# Anemoia-ESP32-SMD.net
KiCad netlist of a schematic drawn in Altium Designer
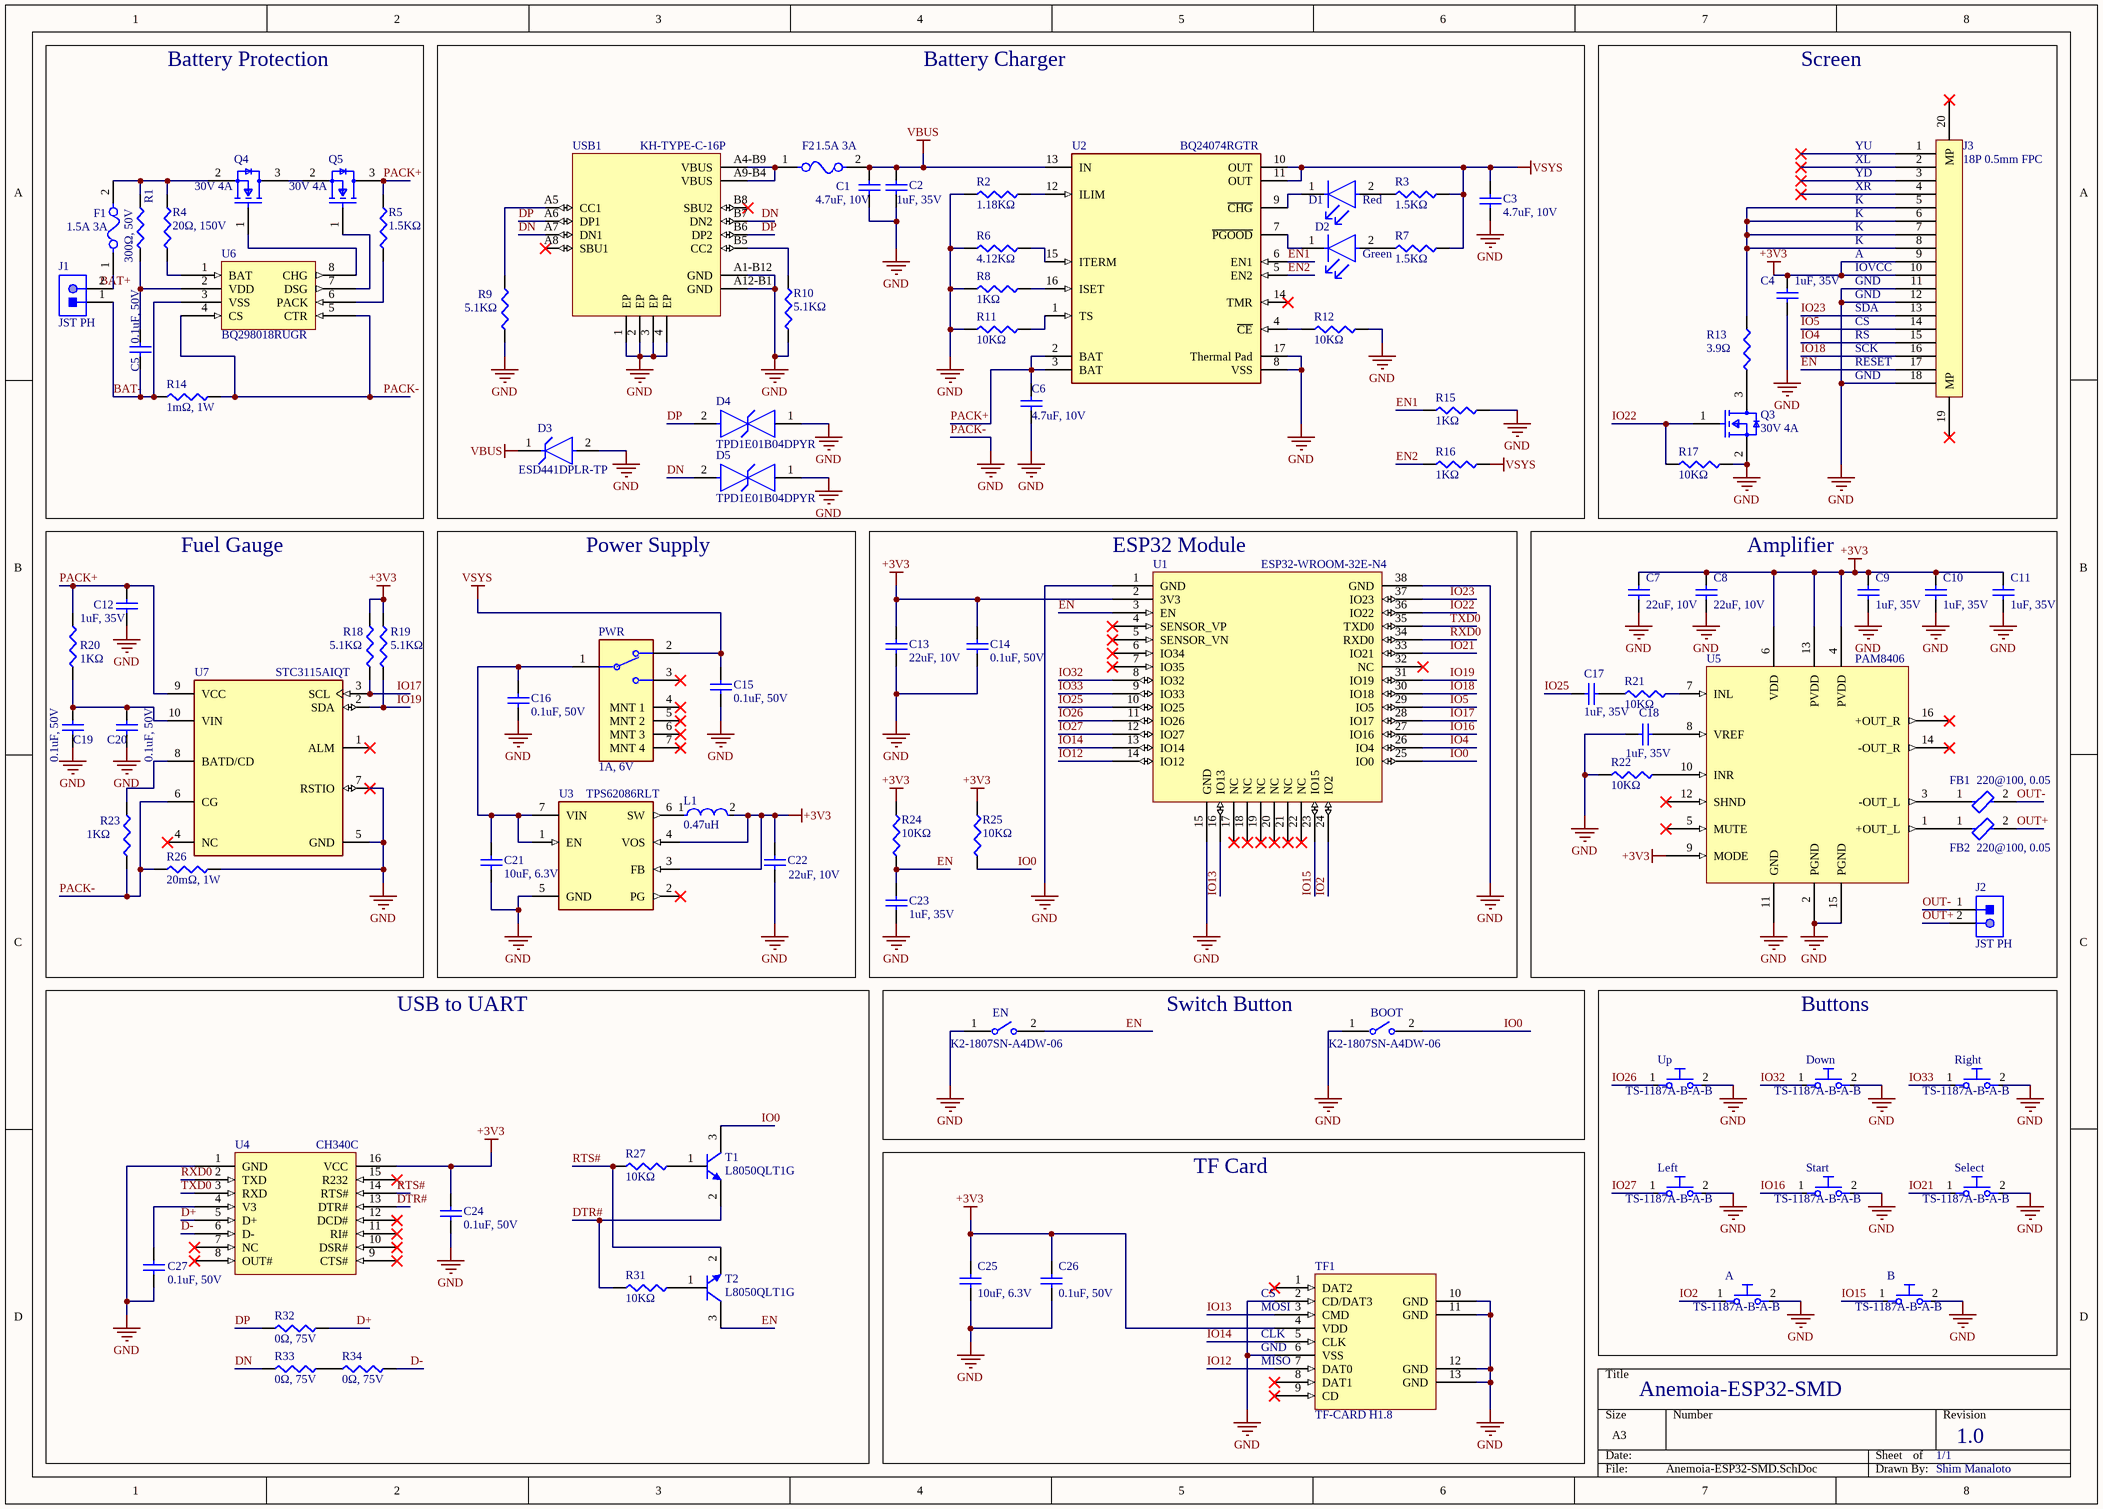
[diagram p0: Anemoia-ESP32-SMD.SchDoc]

(export (version "E")
  (design (tool "Eeschema 10.0.6"))
  (components
    (comp (ref "A")
      (value "TS-1187A-B-A-B")
      (footprint "SWITCH TACTILE SMD-4P,5.1x5.1mm")
      (description "Without Bracket 5.1mm 12V 5.1mm Round Button No SPST 50mA SMD-4P,5.1x5.1mm Tactile Switches RoHS")
      (libsource (lib "Anemoia-ESP32") (part "TS-1187A-B-A-B"))
    )
    (comp (ref "B")
      (value "TS-1187A-B-A-B")
      (footprint "SWITCH TACTILE SMD-4P,5.1x5.1mm")
      (description "Without Bracket 5.1mm 12V 5.1mm Round Button No SPST 50mA SMD-4P,5.1x5.1mm Tactile Switches RoHS")
      (libsource (lib "Anemoia-ESP32") (part "TS-1187A-B-A-B"))
    )
    (comp (ref "BOOT")
      (value "K2-1807SN-A4DW-06")
      (footprint "SWITCH TACTILE MD,4x2.9mm")
      (description "12V 2.9mm 4mm 50mA SMD,4x2.9mm Tactile Switches RoHS")
      (libsource (lib "Anemoia-ESP32") (part "K2-1807SN-A4DW-06"))
    )
    (comp (ref "C1")
      (value "4.7uF, 10V")
      (footprint "CAP CER 0603")
      (description "CAP CER 4.7uF 10V ±10% X5R 0603")
      (fields
        (field (name "MANUFACTURER") "Samsung Electro-Mechanics")
        (field (name "MANUFACTURER PART NUMBER") "CL10A475KP8NNNC")
      )
      (libsource (lib "Anemoia-ESP32") (part "CL10A475KP8NNNC"))
    )
    (comp (ref "C2")
      (value "1uF, 35V")
      (footprint "CAP CER SAMSUNG 0402")
      (description "CAP CER 1uF 35V ±10% X5R 0402")
      (fields
        (field (name "MANUFACTURER") "Samsung Electro-Mechanics")
        (field (name "MANUFACTURER PART NUMBER") "CL05A105KP5NNNC")
      )
      (libsource (lib "Anemoia-ESP32") (part "CL05A105KL5NRNC"))
    )
    (comp (ref "C3")
      (value "4.7uF, 10V")
      (footprint "CAP CER 0603")
      (description "CAP CER 4.7uF 10V ±10% X5R 0603")
      (fields
        (field (name "MANUFACTURER") "Samsung Electro-Mechanics")
        (field (name "MANUFACTURER PART NUMBER") "CL10A475KP8NNNC")
      )
      (libsource (lib "Anemoia-ESP32") (part "CL10A475KP8NNNC"))
    )
    (comp (ref "C4")
      (value "1uF, 35V")
      (footprint "CAP CER SAMSUNG 0402")
      (description "CAP CER 1uF 35V ±10% X5R 0402")
      (fields
        (field (name "MANUFACTURER") "Samsung Electro-Mechanics")
        (field (name "MANUFACTURER PART NUMBER") "CL05A105KP5NNNC")
      )
      (libsource (lib "Anemoia-ESP32") (part "CL05A105KL5NRNC"))
    )
    (comp (ref "C5")
      (value "0.1uF, 50V")
      (footprint "CAP CER 0603")
      (description "CAP CER 0.1UF 50V X7R 0603")
      (fields
        (field (name "MANUFACTURER") "Yageo Group")
        (field (name "MANUFACTURER PART NUMBER") "CC0603KRX7R9BB104")
      )
      (libsource (lib "Anemoia-ESP32") (part "CC0603KRX7R9BB104"))
    )
    (comp (ref "C6")
      (value "4.7uF, 10V")
      (footprint "CAP CER 0603")
      (description "CAP CER 4.7uF 10V ±10% X5R 0603")
      (fields
        (field (name "MANUFACTURER") "Samsung Electro-Mechanics")
        (field (name "MANUFACTURER PART NUMBER") "CL10A475KP8NNNC")
      )
      (libsource (lib "Anemoia-ESP32") (part "CL10A475KP8NNNC"))
    )
    (comp (ref "C7")
      (value "22uF, 10V")
      (footprint "CAP CER 0603")
      (description "CAP CER 22UF 10V X5R 0603")
      (fields
        (field (name "MANUFACTURER") "Murata")
        (field (name "MANUFACTURER PART NUMBER") "GRM188R61A226ME15D")
      )
      (libsource (lib "Anemoia-ESP32") (part "GRM188R61A226ME15D"))
    )
    (comp (ref "C8")
      (value "22uF, 10V")
      (footprint "CAP CER 0603")
      (description "CAP CER 22UF 10V X5R 0603")
      (fields
        (field (name "MANUFACTURER") "Murata")
        (field (name "MANUFACTURER PART NUMBER") "GRM188R61A226ME15D")
      )
      (libsource (lib "Anemoia-ESP32") (part "GRM188R61A226ME15D"))
    )
    (comp (ref "C9")
      (value "1uF, 35V")
      (footprint "CAP CER SAMSUNG 0402")
      (description "CAP CER 1uF 35V ±10% X5R 0402")
      (fields
        (field (name "MANUFACTURER") "Samsung Electro-Mechanics")
        (field (name "MANUFACTURER PART NUMBER") "CL05A105KP5NNNC")
      )
      (libsource (lib "Anemoia-ESP32") (part "CL05A105KL5NRNC"))
    )
    (comp (ref "C10")
      (value "1uF, 35V")
      (footprint "CAP CER SAMSUNG 0402")
      (description "CAP CER 1uF 35V ±10% X5R 0402")
      (fields
        (field (name "MANUFACTURER") "Samsung Electro-Mechanics")
        (field (name "MANUFACTURER PART NUMBER") "CL05A105KP5NNNC")
      )
      (libsource (lib "Anemoia-ESP32") (part "CL05A105KL5NRNC"))
    )
    (comp (ref "C11")
      (value "1uF, 35V")
      (footprint "CAP CER SAMSUNG 0402")
      (description "CAP CER 1uF 35V ±10% X5R 0402")
      (fields
        (field (name "MANUFACTURER") "Samsung Electro-Mechanics")
        (field (name "MANUFACTURER PART NUMBER") "CL05A105KP5NNNC")
      )
      (libsource (lib "Anemoia-ESP32") (part "CL05A105KL5NRNC"))
    )
    (comp (ref "C12")
      (value "1uF, 35V")
      (footprint "CAP CER SAMSUNG 0402")
      (description "CAP CER 1uF 35V ±10% X5R 0402")
      (fields
        (field (name "MANUFACTURER") "Samsung Electro-Mechanics")
        (field (name "MANUFACTURER PART NUMBER") "CL05A105KP5NNNC")
      )
      (libsource (lib "Anemoia-ESP32") (part "CL05A105KL5NRNC"))
    )
    (comp (ref "C13")
      (value "22uF, 10V")
      (footprint "CAP CER 0603")
      (description "CAP CER 22UF 10V X5R 0603")
      (fields
        (field (name "MANUFACTURER") "Murata")
        (field (name "MANUFACTURER PART NUMBER") "GRM188R61A226ME15D")
      )
      (libsource (lib "Anemoia-ESP32") (part "GRM188R61A226ME15D"))
    )
    (comp (ref "C14")
      (value "0.1uF, 50V")
      (footprint "CAP CER 0603")
      (description "CAP CER 0.1UF 50V X7R 0603")
      (fields
        (field (name "MANUFACTURER") "Yageo Group")
        (field (name "MANUFACTURER PART NUMBER") "CC0603KRX7R9BB104")
      )
      (libsource (lib "Anemoia-ESP32") (part "CC0603KRX7R9BB104"))
    )
    (comp (ref "C15")
      (value "0.1uF, 50V")
      (footprint "CAP CER 0603")
      (description "CAP CER 0.1UF 50V X7R 0603")
      (fields
        (field (name "MANUFACTURER") "Yageo Group")
        (field (name "MANUFACTURER PART NUMBER") "CC0603KRX7R9BB104")
      )
      (libsource (lib "Anemoia-ESP32") (part "CC0603KRX7R9BB104"))
    )
    (comp (ref "C16")
      (value "0.1uF, 50V")
      (footprint "CAP CER 0603")
      (description "CAP CER 0.1UF 50V X7R 0603")
      (fields
        (field (name "MANUFACTURER") "Yageo Group")
        (field (name "MANUFACTURER PART NUMBER") "CC0603KRX7R9BB104")
      )
      (libsource (lib "Anemoia-ESP32") (part "CC0603KRX7R9BB104"))
    )
    (comp (ref "C17")
      (value "1uF, 35V")
      (footprint "CAP CER SAMSUNG 0402")
      (description "CAP CER 1uF 35V ±10% X5R 0402")
      (fields
        (field (name "MANUFACTURER") "Samsung Electro-Mechanics")
        (field (name "MANUFACTURER PART NUMBER") "CL05A105KP5NNNC")
      )
      (libsource (lib "Anemoia-ESP32") (part "CL05A105KL5NRNC"))
    )
    (comp (ref "C18")
      (value "1uF, 35V")
      (footprint "CAP CER SAMSUNG 0402")
      (description "CAP CER 1uF 35V ±10% X5R 0402")
      (fields
        (field (name "MANUFACTURER") "Samsung Electro-Mechanics")
        (field (name "MANUFACTURER PART NUMBER") "CL05A105KP5NNNC")
      )
      (libsource (lib "Anemoia-ESP32") (part "CL05A105KL5NRNC"))
    )
    (comp (ref "C19")
      (value "0.1uF, 50V")
      (footprint "CAP CER 0603")
      (description "CAP CER 0.1UF 50V X7R 0603")
      (fields
        (field (name "MANUFACTURER") "Yageo Group")
        (field (name "MANUFACTURER PART NUMBER") "CC0603KRX7R9BB104")
      )
      (libsource (lib "Anemoia-ESP32") (part "CC0603KRX7R9BB104"))
    )
    (comp (ref "C20")
      (value "0.1uF, 50V")
      (footprint "CAP CER 0603")
      (description "CAP CER 0.1UF 50V X7R 0603")
      (fields
        (field (name "MANUFACTURER") "Yageo Group")
        (field (name "MANUFACTURER PART NUMBER") "CC0603KRX7R9BB104")
      )
      (libsource (lib "Anemoia-ESP32") (part "CC0603KRX7R9BB104"))
    )
    (comp (ref "C21")
      (value "10uF, 6.3V")
      (footprint "CAP CER SAMSUNG 0402")
      (description "6.3V 10uF X5R ±20% 0402 Ceramic Capacitors RoHS")
      (fields
        (field (name "MANUFACTURER") "Samsung Electro-Mechanics")
        (field (name "MANUFACTURER PART NUMBER") "CL05A106MQ5NUNC")
      )
      (libsource (lib "Anemoia-ESP32") (part "CL05A106MQ5NUNC"))
    )
    (comp (ref "C22")
      (value "22uF, 10V")
      (footprint "CAP CER 0603")
      (description "CAP CER 22UF 10V X5R 0603")
      (fields
        (field (name "MANUFACTURER") "Murata")
        (field (name "MANUFACTURER PART NUMBER") "GRM188R61A226ME15D")
      )
      (libsource (lib "Anemoia-ESP32") (part "GRM188R61A226ME15D"))
    )
    (comp (ref "C23")
      (value "1uF, 35V")
      (footprint "CAP CER SAMSUNG 0402")
      (description "CAP CER 1uF 35V ±10% X5R 0402")
      (fields
        (field (name "MANUFACTURER") "Samsung Electro-Mechanics")
        (field (name "MANUFACTURER PART NUMBER") "CL05A105KP5NNNC")
      )
      (libsource (lib "Anemoia-ESP32") (part "CL05A105KL5NRNC"))
    )
    (comp (ref "C24")
      (value "0.1uF, 50V")
      (footprint "CAP CER 0603")
      (description "CAP CER 0.1UF 50V X7R 0603")
      (fields
        (field (name "MANUFACTURER") "Yageo Group")
        (field (name "MANUFACTURER PART NUMBER") "CC0603KRX7R9BB104")
      )
      (libsource (lib "Anemoia-ESP32") (part "CC0603KRX7R9BB104"))
    )
    (comp (ref "C25")
      (value "10uF, 6.3V")
      (footprint "CAP CER SAMSUNG 0402")
      (description "6.3V 10uF X5R ±20% 0402 Ceramic Capacitors RoHS")
      (fields
        (field (name "MANUFACTURER") "Samsung Electro-Mechanics")
        (field (name "MANUFACTURER PART NUMBER") "CL05A106MQ5NUNC")
      )
      (libsource (lib "Anemoia-ESP32") (part "CL05A106MQ5NUNC"))
    )
    (comp (ref "C26")
      (value "0.1uF, 50V")
      (footprint "CAP CER 0603")
      (description "CAP CER 0.1UF 50V X7R 0603")
      (fields
        (field (name "MANUFACTURER") "Yageo Group")
        (field (name "MANUFACTURER PART NUMBER") "CC0603KRX7R9BB104")
      )
      (libsource (lib "Anemoia-ESP32") (part "CC0603KRX7R9BB104"))
    )
    (comp (ref "C27")
      (value "0.1uF, 50V")
      (footprint "CAP CER 0603")
      (description "CAP CER 0.1UF 50V X7R 0603")
      (fields
        (field (name "MANUFACTURER") "Yageo Group")
        (field (name "MANUFACTURER PART NUMBER") "CC0603KRX7R9BB104")
      )
      (libsource (lib "Anemoia-ESP32") (part "CC0603KRX7R9BB104"))
    )
    (comp (ref "D1")
      (value "Red")
      (footprint "Red LED 0603")
      (description "LED RED WATER CLEAR 0603 SMD")
      (libsource (lib "Anemoia-ESP32") (part "XL-1608SURC-06"))
    )
    (comp (ref "D2")
      (value "Green")
      (footprint "Green LED 0603")
      (description "LED GREEN WATER CLEAR 0603 SMD")
      (libsource (lib "Anemoia-ESP32") (part "PSC-1608U52GC-G4"))
    )
    (comp (ref "D3")
      (value "ESD441DPLR-TP")
      (footprint "DFN0603-2")
      (description "ESD DIODE 5.5VWM 20VC DFN0603-2")
      (libsource (lib "Anemoia-ESP32") (part "ESD441DPLR-TP"))
    )
    (comp (ref "D4")
      (value "TPD1E01B04DPYR")
      (footprint "X1-SON-2")
      (description "3.6VWM 9VC X1SON-2(0.6x1)")
      (libsource (lib "Anemoia-ESP32") (part "TPD1E01B04DPYR"))
    )
    (comp (ref "D5")
      (value "TPD1E01B04DPYR")
      (footprint "X1-SON-2")
      (description "3.6VWM 9VC X1SON-2(0.6x1)")
      (libsource (lib "Anemoia-ESP32") (part "TPD1E01B04DPYR"))
    )
    (comp (ref "Down")
      (value "TS-1187A-B-A-B")
      (footprint "SWITCH TACTILE SMD-4P,5.1x5.1mm")
      (description "Without Bracket 5.1mm 12V 5.1mm Round Button No SPST 50mA SMD-4P,5.1x5.1mm Tactile Switches RoHS")
      (libsource (lib "Anemoia-ESP32") (part "TS-1187A-B-A-B"))
    )
    (comp (ref "EN")
      (value "K2-1807SN-A4DW-06")
      (footprint "SWITCH TACTILE MD,4x2.9mm")
      (description "12V 2.9mm 4mm 50mA SMD,4x2.9mm Tactile Switches RoHS")
      (libsource (lib "Anemoia-ESP32") (part "K2-1807SN-A4DW-06"))
    )
    (comp (ref "F1")
      (value "1.5A 3A")
      (footprint "PTC 1812")
      (description "24V 1.5A 20A 3A 40mΩ 1812 PTC Resettable Fuses RoHS")
      (fields
        (field (name "MANUFACTURER") "Littelfuse")
        (field (name "MANUFACTURER PART NUMBER") "1812L150/24MR")
      )
      (libsource (lib "Anemoia-ESP32") (part "1812L150/24MR"))
    )
    (comp (ref "F2")
      (value "1.5A 3A")
      (footprint "PTC 1812")
      (description "24V 1.5A 20A 3A 40mΩ 1812 PTC Resettable Fuses RoHS")
      (fields
        (field (name "MANUFACTURER") "Littelfuse")
        (field (name "MANUFACTURER PART NUMBER") "1812L150/24MR")
      )
      (libsource (lib "Anemoia-ESP32") (part "1812L150/24MR"))
    )
    (comp (ref "FB1")
      (value "220@100, 0.05")
      (footprint "0603 FB")
      (description "Chip Ferrite Bead, 0603, 220Ω @ 100MHz, 0.05Ω, 25%, 2A")
      (fields
        (field (name "MANUFACTURER") "Murata")
        (field (name "MANUFACTURER PART NUMBER") "BLM18EG221SN1D")
      )
      (libsource (lib "Anemoia-ESP32") (part "BLM18EG221SN1D"))
    )
    (comp (ref "FB2")
      (value "220@100, 0.05")
      (footprint "0603 FB")
      (description "Chip Ferrite Bead, 0603, 220Ω @ 100MHz, 0.05Ω, 25%, 2A")
      (fields
        (field (name "MANUFACTURER") "Murata")
        (field (name "MANUFACTURER PART NUMBER") "BLM18EG221SN1D")
      )
      (libsource (lib "Anemoia-ESP32") (part "BLM18EG221SN1D"))
    )
    (comp (ref "J1")
      (value "JST PH")
      (footprint "JST_S2B-PH-SM4-TB(LF)(SN)")
      (fields
        (field (name "MANUFACTURER") "JST")
        (field (name "MANUFACTURER PART NUMBER") "S2B-PH-SM4-TB(LF)(SN)")
      )
      (libsource (lib "") (part "S2B-PH-SM4-TB(LF)(SN)_1"))
    )
    (comp (ref "J2")
      (value "JST PH")
      (footprint "JST_S2B-PH-SM4-TB(LF)(SN)")
      (fields
        (field (name "MANUFACTURER") "JST")
        (field (name "MANUFACTURER PART NUMBER") "S2B-PH-SM4-TB(LF)(SN)")
      )
      (libsource (lib "Anemoia-ESP32") (part "S2B-PH-SM4-TB(LF)(SN)"))
    )
    (comp (ref "J3")
      (value "18P 0.5mm FPC")
      (footprint "FPC CN 18P 0.5mm")
      (description "CONN FFC FPC 18POS 0.5mm BOTTOM CNT SMD R/A")
      (libsource (lib "Anemoia-ESP32") (part "HC-FPC-0.5-18P-CXH20"))
    )
    (comp (ref "L1")
      (value "0.47uH")
      (footprint "SMD,4x4mm")
      (description "FIXED IND 470nH SMD,4x4mm")
      (libsource (lib "Anemoia-ESP32") (part "XFL4015-471MEC"))
    )
    (comp (ref "Left")
      (value "TS-1187A-B-A-B")
      (footprint "SWITCH TACTILE SMD-4P,5.1x5.1mm")
      (description "Without Bracket 5.1mm 12V 5.1mm Round Button No SPST 50mA SMD-4P,5.1x5.1mm Tactile Switches RoHS")
      (libsource (lib "Anemoia-ESP32") (part "TS-1187A-B-A-B"))
    )
    (comp (ref "PWR")
      (value "1A, 6V")
      (footprint "MK-12C02-G020")
      (description "Surface Mount, Right Angle 1A SPDT 6V Black 10,000 Cycles SMD,6.6x1.4mm Slide Switches RoHS")
      (libsource (lib "Anemoia-ESP32") (part "MK-12C02-G020"))
    )
    (comp (ref "Q3")
      (value "30V 4A")
      (footprint "SOT-23")
      (description "MOSFET N-CH 30V SOT-23")
      (libsource (lib "Anemoia-ESP32") (part "AO3402"))
    )
    (comp (ref "Q4")
      (value "30V 4A")
      (footprint "SOT-23")
      (description "MOSFET N-CH 30V SOT-23")
      (libsource (lib "Anemoia-ESP32") (part "AO3402"))
    )
    (comp (ref "Q5")
      (value "30V 4A")
      (footprint "SOT-23")
      (description "MOSFET N-CH 30V SOT-23")
      (libsource (lib "Anemoia-ESP32") (part "AO3402"))
    )
    (comp (ref "R1")
      (value "300Ω, 50V")
      (footprint "RES 0402")
      (description "RES 300Ω ±1% 62.5mW 0402")
      (libsource (lib "Anemoia-ESP32") (part "RC0402FR-07300RL"))
    )
    (comp (ref "R2")
      (value "1.18KΩ")
      (footprint "RES 0402")
      (description "RES 1.18kΩ ±1% 62.5mW 0402")
      (libsource (lib "Anemoia-ESP32") (part "RC0402FR-071K18L"))
    )
    (comp (ref "R3")
      (value "1.5KΩ")
      (footprint "RES 0603")
      (description "RES 1.5kΩ ±1% 100mW 0603")
      (libsource (lib "Anemoia-ESP32") (part "RC0603FR-071K5L"))
    )
    (comp (ref "R4")
      (value "20Ω, 150V")
      (footprint "RES 0805")
      (description "RES 20Ω ±1% 125mW 0805")
      (libsource (lib "Anemoia-ESP32") (part "RC0805FR-0720RL"))
    )
    (comp (ref "R5")
      (value "1.5KΩ")
      (footprint "RES 0603")
      (description "RES 1.5kΩ ±1% 100mW 0603")
      (libsource (lib "Anemoia-ESP32") (part "RC0603FR-071K5L"))
    )
    (comp (ref "R6")
      (value "4.12KΩ")
      (footprint "RES 0402")
      (description "RES 4.12kΩ ±1% 62.5mW 0402")
      (libsource (lib "Anemoia-ESP32") (part "RC0402FR-074K12L"))
    )
    (comp (ref "R7")
      (value "1.5KΩ")
      (footprint "RES 0603")
      (description "RES 1.5kΩ ±1% 100mW 0603")
      (libsource (lib "Anemoia-ESP32") (part "RC0603FR-071K5L"))
    )
    (comp (ref "R8")
      (value "1KΩ")
      (footprint "RES 0402")
      (description "RES 1kΩ ±1% 62.5mW 0402")
      (fields
        (field (name "MANUFACTURER") "Yageo Group")
        (field (name "MANUFACTURER PART NUMBER") "RC0402FR-071KL")
      )
      (libsource (lib "Anemoia-ESP32") (part "RC0402FR-071KL"))
    )
    (comp (ref "R9")
      (value "5.1KΩ")
      (footprint "RES 0402")
      (description "RES 5.1kΩ ±1% 62.5mW 0402")
      (libsource (lib "Anemoia-ESP32") (part "RC0402FR-075K1L"))
    )
    (comp (ref "R10")
      (value "5.1KΩ")
      (footprint "RES 0402")
      (description "RES 5.1kΩ ±1% 62.5mW 0402")
      (libsource (lib "Anemoia-ESP32") (part "RC0402FR-075K1L"))
    )
    (comp (ref "R11")
      (value "10KΩ")
      (footprint "RES 0402")
      (description "RES 10K OHM 1% 1/16W 0402")
      (fields
        (field (name "MANUFACTURER") "Yageo Group")
        (field (name "MANUFACTURER PART NUMBER") "RC0402FR-0710KL")
      )
      (libsource (lib "Anemoia-ESP32") (part "RC0402FR-0710KL"))
    )
    (comp (ref "R12")
      (value "10KΩ")
      (footprint "RES 0402")
      (description "RES 10K OHM 1% 1/16W 0402")
      (fields
        (field (name "MANUFACTURER") "Yageo Group")
        (field (name "MANUFACTURER PART NUMBER") "RC0402FR-0710KL")
      )
      (libsource (lib "Anemoia-ESP32") (part "RC0402FR-0710KL"))
    )
    (comp (ref "R13")
      (value "3.9Ω")
      (footprint "RES 0612")
      (description "RES 3.9Ω ±5% 750mW 0612")
      (fields (field (name "MANUFACTURER") "ROHM") (field (name "MANUFACTURER PART NUMBER") "LTR18EZPJ3R9"))
      (libsource (lib "Anemoia-ESP32") (part "LTR18EZPJ3R9"))
    )
    (comp (ref "R14")
      (value "1mΩ, 1W")
      (footprint "RES 1206")
      (description "RES 1mΩ ±1% 1W 1206")
      (libsource (lib "Anemoia-ESP32") (part "FRM121WFR001TM"))
    )
    (comp (ref "R15")
      (value "1KΩ")
      (footprint "RES 0402")
      (description "RES 1kΩ ±1% 62.5mW 0402")
      (fields
        (field (name "MANUFACTURER") "Yageo Group")
        (field (name "MANUFACTURER PART NUMBER") "RC0402FR-071KL")
      )
      (libsource (lib "Anemoia-ESP32") (part "RC0402FR-071KL"))
    )
    (comp (ref "R16")
      (value "1KΩ")
      (footprint "RES 0402")
      (description "RES 1kΩ ±1% 62.5mW 0402")
      (fields
        (field (name "MANUFACTURER") "Yageo Group")
        (field (name "MANUFACTURER PART NUMBER") "RC0402FR-071KL")
      )
      (libsource (lib "Anemoia-ESP32") (part "RC0402FR-071KL"))
    )
    (comp (ref "R17")
      (value "10KΩ")
      (footprint "RES 0402")
      (description "RES 10K OHM 1% 1/16W 0402")
      (fields
        (field (name "MANUFACTURER") "Yageo Group")
        (field (name "MANUFACTURER PART NUMBER") "RC0402FR-0710KL")
      )
      (libsource (lib "Anemoia-ESP32") (part "RC0402FR-0710KL"))
    )
    (comp (ref "R18")
      (value "5.1KΩ")
      (footprint "RES 0402")
      (description "RES 5.1kΩ ±1% 62.5mW 0402")
      (libsource (lib "Anemoia-ESP32") (part "RC0402FR-075K1L"))
    )
    (comp (ref "R19")
      (value "5.1KΩ")
      (footprint "RES 0402")
      (description "RES 5.1kΩ ±1% 62.5mW 0402")
      (libsource (lib "Anemoia-ESP32") (part "RC0402FR-075K1L"))
    )
    (comp (ref "R20")
      (value "1KΩ")
      (footprint "RES 0402")
      (description "RES 1kΩ ±1% 62.5mW 0402")
      (fields
        (field (name "MANUFACTURER") "Yageo Group")
        (field (name "MANUFACTURER PART NUMBER") "RC0402FR-071KL")
      )
      (libsource (lib "Anemoia-ESP32") (part "RC0402FR-071KL"))
    )
    (comp (ref "R21")
      (value "10KΩ")
      (footprint "RES 0402")
      (description "RES 10K OHM 1% 1/16W 0402")
      (fields
        (field (name "MANUFACTURER") "Yageo Group")
        (field (name "MANUFACTURER PART NUMBER") "RC0402FR-0710KL")
      )
      (libsource (lib "Anemoia-ESP32") (part "RC0402FR-0710KL"))
    )
    (comp (ref "R22")
      (value "10KΩ")
      (footprint "RES 0402")
      (description "RES 10K OHM 1% 1/16W 0402")
      (fields
        (field (name "MANUFACTURER") "Yageo Group")
        (field (name "MANUFACTURER PART NUMBER") "RC0402FR-0710KL")
      )
      (libsource (lib "Anemoia-ESP32") (part "RC0402FR-0710KL"))
    )
    (comp (ref "R23")
      (value "1KΩ")
      (footprint "RES 0402")
      (description "RES 1kΩ ±1% 62.5mW 0402")
      (fields
        (field (name "MANUFACTURER") "Yageo Group")
        (field (name "MANUFACTURER PART NUMBER") "RC0402FR-071KL")
      )
      (libsource (lib "Anemoia-ESP32") (part "RC0402FR-071KL"))
    )
    (comp (ref "R24")
      (value "10KΩ")
      (footprint "RES 0402")
      (description "RES 10K OHM 1% 1/16W 0402")
      (fields
        (field (name "MANUFACTURER") "Yageo Group")
        (field (name "MANUFACTURER PART NUMBER") "RC0402FR-0710KL")
      )
      (libsource (lib "Anemoia-ESP32") (part "RC0402FR-0710KL"))
    )
    (comp (ref "R25")
      (value "10KΩ")
      (footprint "RES 0402")
      (description "RES 10K OHM 1% 1/16W 0402")
      (fields
        (field (name "MANUFACTURER") "Yageo Group")
        (field (name "MANUFACTURER PART NUMBER") "RC0402FR-0710KL")
      )
      (libsource (lib "Anemoia-ESP32") (part "RC0402FR-0710KL"))
    )
    (comp (ref "R26")
      (value "20mΩ, 1W")
      (footprint "RES 1206")
      (description "RES 20mΩ ±1% 1W 1206")
      (libsource (lib "Anemoia-ESP32") (part "FRM121WFR020TM"))
    )
    (comp (ref "R27")
      (value "10KΩ")
      (footprint "RES 0402")
      (description "RES 10K OHM 1% 1/16W 0402")
      (fields
        (field (name "MANUFACTURER") "Yageo Group")
        (field (name "MANUFACTURER PART NUMBER") "RC0402FR-0710KL")
      )
      (libsource (lib "Anemoia-ESP32") (part "RC0402FR-0710KL"))
    )
    (comp (ref "R31")
      (value "10KΩ")
      (footprint "RES 0402")
      (description "RES 10K OHM 1% 1/16W 0402")
      (fields
        (field (name "MANUFACTURER") "Yageo Group")
        (field (name "MANUFACTURER PART NUMBER") "RC0402FR-0710KL")
      )
      (libsource (lib "Anemoia-ESP32") (part "RC0402FR-0710KL"))
    )
    (comp (ref "R32")
      (value "0Ω, 75V")
      (footprint "RES 0OHM")
      (description "RES 0Ω ±1% 100mW 0603")
      (fields
        (field (name "MANUFACTURER") "Yageo Group")
        (field (name "MANUFACTURER PART NUMBER") "RC0603FR-070RL")
      )
      (libsource (lib "Anemoia-ESP32") (part "RC0603FR-070RL"))
    )
    (comp (ref "R33")
      (value "0Ω, 75V")
      (footprint "RES 0OHM")
      (description "RES 0Ω ±1% 100mW 0603")
      (fields
        (field (name "MANUFACTURER") "Yageo Group")
        (field (name "MANUFACTURER PART NUMBER") "RC0603FR-070RL")
      )
      (libsource (lib "Anemoia-ESP32") (part "RC0603FR-070RL"))
    )
    (comp (ref "R34")
      (value "0Ω, 75V")
      (footprint "RES 0OHM")
      (description "RES 0Ω ±1% 100mW 0603")
      (fields
        (field (name "MANUFACTURER") "Yageo Group")
        (field (name "MANUFACTURER PART NUMBER") "RC0603FR-070RL")
      )
      (libsource (lib "Anemoia-ESP32") (part "RC0603FR-070RL"))
    )
    (comp (ref "Right")
      (value "TS-1187A-B-A-B")
      (footprint "SWITCH TACTILE SMD-4P,5.1x5.1mm")
      (description "Without Bracket 5.1mm 12V 5.1mm Round Button No SPST 50mA SMD-4P,5.1x5.1mm Tactile Switches RoHS")
      (libsource (lib "Anemoia-ESP32") (part "TS-1187A-B-A-B"))
    )
    (comp (ref "Select")
      (value "TS-1187A-B-A-B")
      (footprint "SWITCH TACTILE SMD-4P,5.1x5.1mm")
      (description "Without Bracket 5.1mm 12V 5.1mm Round Button No SPST 50mA SMD-4P,5.1x5.1mm Tactile Switches RoHS")
      (libsource (lib "Anemoia-ESP32") (part "TS-1187A-B-A-B"))
    )
    (comp (ref "Start")
      (value "TS-1187A-B-A-B")
      (footprint "SWITCH TACTILE SMD-4P,5.1x5.1mm")
      (description "Without Bracket 5.1mm 12V 5.1mm Round Button No SPST 50mA SMD-4P,5.1x5.1mm Tactile Switches RoHS")
      (libsource (lib "Anemoia-ESP32") (part "TS-1187A-B-A-B"))
    )
    (comp (ref "T1")
      (value "L8050QLT1G")
      (footprint "SOT-23")
      (description "TRANS NPN 25V 800mA SOT-23")
      (libsource (lib "Anemoia-ESP32") (part "L8050QLT1G"))
    )
    (comp (ref "T2")
      (value "L8050QLT1G")
      (footprint "SOT-23")
      (description "TRANS NPN 25V 800mA SOT-23")
      (libsource (lib "Anemoia-ESP32") (part "L8050QLT1G"))
    )
    (comp (ref "TF1")
      (value "TF-CARD H1.8")
      (footprint "TF-CARD H1.8")
      (description "Push-Push 1.8mm MicroSD Card (TF Card) SMD PC Card Sockets RoHS")
      (libsource (lib "Anemoia-ESP32") (part "TF-CARD H1.8"))
    )
    (comp (ref "U1")
      (value "ESP32-WROOM-32E-N4")
      (footprint "ESP32-WROOM-32E-N4")
      (description "WLAN+BT Module 2412MHz to 2484MHz 47-Pin SMD Module")
      (fields (field (name "MANUFACTURER") "Espressif Systems"))
      (libsource (lib "Anemoia-ESP32") (part "ESP32-WROOM-32E-N4"))
    )
    (comp (ref "U2")
      (value "BQ24074RGTR")
      (footprint "BQ24074RGTR")
      (description "IC BATT CHG LI-ION 1CELL 16QFN")
      (fields (field (name "MANUFACTURER") "Texas Instruments"))
      (libsource (lib "Anemoia-ESP32") (part "BQ24074RGTR"))
    )
    (comp (ref "U3")
      (value "TPS62086RLT")
      (footprint "VSON-7(2x2)")
      (description "2.4MHz Buck 3A Fixed 3.3V 1 VSON-7(2x2) Voltage Regulators - DC DC Switching Regulators RoHS")
      (fields
        (field (name "MANUFACTURER") "Texas Instruments")
        (field (name "MANUFACTURER PART NUMBER") "TPS62086RLTR")
      )
      (libsource (lib "Anemoia-ESP32") (part "TPS62086RLTR"))
    )
    (comp (ref "U4")
      (value "CH340C")
      (footprint "SOP-16")
      (description "USB to Serial Port chip")
      (libsource (lib "Anemoia-ESP32") (part "CH340C"))
    )
    (comp (ref "U5")
      (value "PAM8406")
      (footprint "SOP-16")
      (description "5W Stereo Audio Amplifier")
      (libsource (lib "Anemoia-ESP32") (part "PAM8406"))
    )
    (comp (ref "U6")
      (value "BQ298018RUGR")
      (footprint "X2-QFN-8(1.5x1.5)")
      (description "High-side protector for single-cell li-ion and li-polymer batteries 8-X2QFN -40 to 85")
      (fields (field (name "MANUFACTURER") "Texas Instruments"))
      (libsource (lib "Anemoia-ESP32") (part "BQ298018RUGR"))
    )
    (comp (ref "U7")
      (value "STC3115AIQT")
      (footprint "DFN-10(2x3)")
      (description "Battery Fuel Gauge, Li-Ion, Li-Pol, 2.7V to 4.2V Supply, I2C Interface, DFN-10")
      (fields (field (name "MANUFACTURER") "STMicroelectronics"))
      (libsource (lib "Anemoia-ESP32") (part "STC3115AIQT"))
    )
    (comp (ref "Up")
      (value "TS-1187A-B-A-B")
      (footprint "SWITCH TACTILE SMD-4P,5.1x5.1mm")
      (description "Without Bracket 5.1mm 12V 5.1mm Round Button No SPST 50mA SMD-4P,5.1x5.1mm Tactile Switches RoHS")
      (libsource (lib "Anemoia-ESP32") (part "TS-1187A-B-A-B"))
    )
    (comp (ref "USB1")
      (value "KH-TYPE-C-16P")
      (footprint "USB-C-SMD_KH-TYPE-C-16P")
      (description "CONN RCPT Type-C 16POS SMD R/A")
      (libsource (lib "Anemoia-ESP32") (part "KH-TYPE-C-16P"))
    )
  )
  (nets
    (net (code "1") (name "+3V3") (class "Default")
      (node (ref "C10") (pin "2") (pinfunction "2_2") (pintype "passive"))
      (node (ref "C11") (pin "2") (pinfunction "2_2") (pintype "passive"))
      (node (ref "C13") (pin "1") (pinfunction "1_1") (pintype "passive"))
      (node (ref "C14") (pin "2") (pinfunction "2_2") (pintype "passive"))
      (node (ref "C22") (pin "2") (pinfunction "2_2") (pintype "passive"))
      (node (ref "C24") (pin "1") (pinfunction "1_1") (pintype "passive"))
      (node (ref "C25") (pin "2") (pinfunction "2_2") (pintype "passive"))
      (node (ref "C26") (pin "2") (pinfunction "2_2") (pintype "passive"))
      (node (ref "C4") (pin "2") (pinfunction "2_2") (pintype "passive"))
      (node (ref "C7") (pin "2") (pinfunction "2_2") (pintype "passive"))
      (node (ref "C8") (pin "2") (pinfunction "2_2") (pintype "passive"))
      (node (ref "C9") (pin "2") (pinfunction "2_2") (pintype "passive"))
      (node (ref "J3") (pin "10") (pintype "passive"))
      (node (ref "J3") (pin "9") (pintype "passive"))
      (node (ref "L1") (pin "2") (pinfunction "2_2") (pintype "passive"))
      (node (ref "R18") (pin "2") (pinfunction "2_2") (pintype "passive"))
      (node (ref "R19") (pin "2") (pinfunction "2_2") (pintype "passive"))
      (node (ref "R24") (pin "1") (pinfunction "1_1") (pintype "passive"))
      (node (ref "R25") (pin "1") (pinfunction "1_1") (pintype "passive"))
      (node (ref "TF1") (pin "4") (pinfunction "VDD_4") (pintype "power_in"))
      (node (ref "U1") (pin "2") (pinfunction "3V3_2") (pintype "power_in"))
      (node (ref "U3") (pin "3") (pinfunction "FB_3") (pintype "input"))
      (node (ref "U3") (pin "4") (pinfunction "VOS_4") (pintype "input"))
      (node (ref "U4") (pin "16") (pinfunction "VCC_16") (pintype "power_in"))
      (node (ref "U5") (pin "13") (pinfunction "PVDD_13") (pintype "power_in"))
      (node (ref "U5") (pin "4") (pinfunction "PVDD_4") (pintype "power_in"))
      (node (ref "U5") (pin "6") (pinfunction "VDD_6") (pintype "power_in"))
      (node (ref "U5") (pin "9") (pinfunction "MODE_9") (pintype "input"))
    )
    (net (code "3") (name "/BAT-") (class "Default")
      (node (ref "C5") (pin "1") (pinfunction "1_1") (pintype "passive"))
      (node (ref "J1") (pin "1") (pinfunction "1_1") (pintype "passive"))
      (node (ref "R14") (pin "1") (pinfunction "1_1") (pintype "passive"))
      (node (ref "U6") (pin "3") (pinfunction "VSS_3") (pintype "power_in"))
    )
    (net (code "4") (name "/D+") (class "Default")
      (node (ref "R32") (pin "2") (pinfunction "2_2") (pintype "passive"))
      (node (ref "U4") (pin "5") (pinfunction "D+_5") (pintype "input"))
    )
    (net (code "5") (name "/D-") (class "Default")
      (node (ref "R34") (pin "2") (pinfunction "2_2") (pintype "passive"))
      (node (ref "U4") (pin "6") (pinfunction "D-_6") (pintype "input"))
    )
    (net (code "6") (name "/DN") (class "Default")
      (node (ref "D5") (pin "2") (pinfunction "GND_2") (pintype "passive"))
      (node (ref "R33") (pin "1") (pinfunction "1_1") (pintype "passive"))
      (node (ref "USB1") (pin "A7") (pinfunction "DN1_A7") (pintype "bidirectional"))
      (node (ref "USB1") (pin "B7") (pinfunction "DN2_B7") (pintype "bidirectional"))
    )
    (net (code "7") (name "/DP") (class "Default")
      (node (ref "D4") (pin "2") (pinfunction "GND_2") (pintype "passive"))
      (node (ref "R32") (pin "1") (pinfunction "1_1") (pintype "passive"))
      (node (ref "USB1") (pin "A6") (pinfunction "DP1_A6") (pintype "bidirectional"))
      (node (ref "USB1") (pin "B6") (pinfunction "DP2_B6") (pintype "bidirectional"))
    )
    (net (code "8") (name "/DTR#") (class "Default")
      (node (ref "R31") (pin "1") (pinfunction "1_1") (pintype "passive"))
      (node (ref "T1") (pin "2") (pinfunction "E_2") (pintype "passive"))
      (node (ref "U4") (pin "13") (pinfunction "DTR#_13") (pintype "input"))
    )
    (net (code "9") (name "/EN") (class "Default")
      (node (ref "C23") (pin "1") (pinfunction "1_1") (pintype "passive"))
      (node (ref "EN") (pin "2") (pinfunction "2_2") (pintype "passive"))
      (node (ref "J3") (pin "17") (pintype "passive"))
      (node (ref "R24") (pin "2") (pinfunction "2_2") (pintype "passive"))
      (node (ref "T2") (pin "3") (pinfunction "C_3") (pintype "passive"))
      (node (ref "U1") (pin "3") (pinfunction "EN_3") (pintype "input"))
    )
    (net (code "10") (name "/EN1") (class "Default")
      (node (ref "R15") (pin "1") (pinfunction "1_1") (pintype "passive"))
      (node (ref "U2") (pin "6") (pinfunction "EN1_6") (pintype "input"))
    )
    (net (code "11") (name "/EN2") (class "Default")
      (node (ref "R16") (pin "1") (pinfunction "1_1") (pintype "passive"))
      (node (ref "U2") (pin "5") (pinfunction "EN2_5") (pintype "input"))
    )
    (net (code "12") (name "/IO0") (class "Default")
      (node (ref "BOOT") (pin "2") (pinfunction "2_2") (pintype "passive"))
      (node (ref "R25") (pin "2") (pinfunction "2_2") (pintype "passive"))
      (node (ref "T1") (pin "3") (pinfunction "C_3") (pintype "passive"))
      (node (ref "U1") (pin "25") (pinfunction "IO0_25") (pintype "bidirectional"))
    )
    (net (code "13") (name "/IO2") (class "Default")
      (node (ref "A") (pin "1") (pintype "passive"))
      (node (ref "U1") (pin "24") (pinfunction "IO2_24") (pintype "bidirectional"))
    )
    (net (code "14") (name "/IO4") (class "Default")
      (node (ref "J3") (pin "15") (pintype "passive"))
      (node (ref "U1") (pin "26") (pinfunction "IO4_26") (pintype "bidirectional"))
    )
    (net (code "15") (name "/IO5") (class "Default")
      (node (ref "J3") (pin "14") (pintype "passive"))
      (node (ref "U1") (pin "29") (pinfunction "IO5_29") (pintype "bidirectional"))
    )
    (net (code "16") (name "/IO12") (class "Default")
      (node (ref "TF1") (pin "7") (pinfunction "DAT0_7") (pintype "input"))
      (node (ref "U1") (pin "14") (pinfunction "IO12_14") (pintype "bidirectional"))
    )
    (net (code "17") (name "/IO13") (class "Default")
      (node (ref "TF1") (pin "3") (pinfunction "CMD_3") (pintype "input"))
      (node (ref "U1") (pin "16") (pinfunction "IO13_16") (pintype "bidirectional"))
    )
    (net (code "18") (name "/IO14") (class "Default")
      (node (ref "TF1") (pin "5") (pinfunction "CLK_5") (pintype "input"))
      (node (ref "U1") (pin "13") (pinfunction "IO14_13") (pintype "bidirectional"))
    )
    (net (code "19") (name "/IO15") (class "Default")
      (node (ref "B") (pin "1") (pintype "passive"))
      (node (ref "U1") (pin "23") (pinfunction "IO15_23") (pintype "bidirectional"))
    )
    (net (code "20") (name "/IO16") (class "Default")
      (node (ref "Start") (pin "1") (pintype "passive"))
      (node (ref "U1") (pin "27") (pinfunction "IO16_27") (pintype "bidirectional"))
    )
    (net (code "21") (name "/IO17") (class "Default")
      (node (ref "R18") (pin "1") (pinfunction "1_1") (pintype "passive"))
      (node (ref "U1") (pin "28") (pinfunction "IO17_28") (pintype "bidirectional"))
      (node (ref "U7") (pin "3") (pinfunction "SCL_3") (pintype "input"))
    )
    (net (code "22") (name "/IO18") (class "Default")
      (node (ref "J3") (pin "16") (pintype "passive"))
      (node (ref "U1") (pin "30") (pinfunction "IO18_30") (pintype "bidirectional"))
    )
    (net (code "23") (name "/IO19") (class "Default")
      (node (ref "R19") (pin "1") (pinfunction "1_1") (pintype "passive"))
      (node (ref "U1") (pin "31") (pinfunction "IO19_31") (pintype "bidirectional"))
      (node (ref "U7") (pin "2") (pinfunction "SDA_2") (pintype "bidirectional"))
    )
    (net (code "24") (name "/IO21") (class "Default")
      (node (ref "Select") (pin "1") (pintype "passive"))
      (node (ref "U1") (pin "33") (pinfunction "IO21_33") (pintype "bidirectional"))
    )
    (net (code "25") (name "/IO22") (class "Default")
      (node (ref "Q3") (pin "1") (pinfunction "gate_1") (pintype "passive"))
      (node (ref "R17") (pin "2") (pinfunction "2_2") (pintype "passive"))
      (node (ref "U1") (pin "36") (pinfunction "IO22_36") (pintype "bidirectional"))
    )
    (net (code "26") (name "/IO23") (class "Default")
      (node (ref "J3") (pin "13") (pintype "passive"))
      (node (ref "U1") (pin "37") (pinfunction "IO23_37") (pintype "bidirectional"))
    )
    (net (code "27") (name "/IO25") (class "Default")
      (node (ref "C17") (pin "2") (pinfunction "2_2") (pintype "passive"))
      (node (ref "U1") (pin "10") (pinfunction "IO25_10") (pintype "bidirectional"))
    )
    (net (code "28") (name "/IO26") (class "Default")
      (node (ref "U1") (pin "11") (pinfunction "IO26_11") (pintype "bidirectional"))
      (node (ref "Up") (pin "1") (pintype "passive"))
    )
    (net (code "29") (name "/IO27") (class "Default")
      (node (ref "Left") (pin "1") (pintype "passive"))
      (node (ref "U1") (pin "12") (pinfunction "IO27_12") (pintype "bidirectional"))
    )
    (net (code "30") (name "/IO32") (class "Default")
      (node (ref "Down") (pin "1") (pintype "passive"))
      (node (ref "U1") (pin "8") (pinfunction "IO32_8") (pintype "bidirectional"))
    )
    (net (code "31") (name "/IO33") (class "Default")
      (node (ref "Right") (pin "1") (pintype "passive"))
      (node (ref "U1") (pin "9") (pinfunction "IO33_9") (pintype "bidirectional"))
    )
    (net (code "32") (name "/OUT+") (class "Default")
      (node (ref "FB2") (pin "2") (pinfunction "2_2") (pintype "passive"))
      (node (ref "J2") (pin "2") (pinfunction "2_2") (pintype "passive"))
    )
    (net (code "33") (name "/OUT-") (class "Default")
      (node (ref "FB1") (pin "2") (pinfunction "2_2") (pintype "passive"))
      (node (ref "J2") (pin "1") (pinfunction "1_1") (pintype "passive"))
    )
    (net (code "34") (name "/PACK+") (class "Default")
      (node (ref "C12") (pin "2") (pinfunction "2_2") (pintype "passive"))
      (node (ref "C6") (pin "2") (pinfunction "2_2") (pintype "passive"))
      (node (ref "Q5") (pin "3") (pinfunction "drain_3") (pintype "passive"))
      (node (ref "R20") (pin "2") (pinfunction "2_2") (pintype "passive"))
      (node (ref "R5") (pin "2") (pinfunction "2_2") (pintype "passive"))
      (node (ref "U2") (pin "2") (pinfunction "BAT_2") (pintype "power_in"))
      (node (ref "U2") (pin "3") (pinfunction "BAT_3") (pintype "power_in"))
      (node (ref "U7") (pin "9") (pinfunction "VCC_9") (pintype "power_in"))
    )
    (net (code "35") (name "/RTS#") (class "Default")
      (node (ref "R27") (pin "1") (pinfunction "1_1") (pintype "passive"))
      (node (ref "T2") (pin "2") (pinfunction "E_2") (pintype "passive"))
      (node (ref "U4") (pin "14") (pinfunction "RTS#_14") (pintype "input"))
    )
    (net (code "36") (name "/RXD0") (class "Default")
      (node (ref "U1") (pin "34") (pinfunction "RXD0_34") (pintype "bidirectional"))
      (node (ref "U4") (pin "2") (pinfunction "TXD_2") (pintype "input"))
    )
    (net (code "37") (name "/TXD0") (class "Default")
      (node (ref "U1") (pin "35") (pinfunction "TXD0_35") (pintype "bidirectional"))
      (node (ref "U4") (pin "3") (pinfunction "RXD_3") (pintype "input"))
    )
    (net (code "38") (name "GND") (class "Default")
      (node (ref "A") (pin "2") (pintype "passive"))
      (node (ref "B") (pin "2") (pintype "passive"))
      (node (ref "BOOT") (pin "1") (pinfunction "1_1") (pintype "passive"))
      (node (ref "C1") (pin "1") (pinfunction "1_1") (pintype "passive"))
      (node (ref "C10") (pin "1") (pinfunction "1_1") (pintype "passive"))
      (node (ref "C11") (pin "1") (pinfunction "1_1") (pintype "passive"))
      (node (ref "C12") (pin "1") (pinfunction "1_1") (pintype "passive"))
      (node (ref "C13") (pin "2") (pinfunction "2_2") (pintype "passive"))
      (node (ref "C14") (pin "1") (pinfunction "1_1") (pintype "passive"))
      (node (ref "C15") (pin "1") (pinfunction "1_1") (pintype "passive"))
      (node (ref "C16") (pin "1") (pinfunction "1_1") (pintype "passive"))
      (node (ref "C18") (pin "1") (pinfunction "1_1") (pintype "passive"))
      (node (ref "C19") (pin "1") (pinfunction "1_1") (pintype "passive"))
      (node (ref "C2") (pin "2") (pinfunction "2_2") (pintype "passive"))
      (node (ref "C20") (pin "1") (pinfunction "1_1") (pintype "passive"))
      (node (ref "C21") (pin "2") (pinfunction "2_2") (pintype "passive"))
      (node (ref "C22") (pin "1") (pinfunction "1_1") (pintype "passive"))
      (node (ref "C23") (pin "2") (pinfunction "2_2") (pintype "passive"))
      (node (ref "C24") (pin "2") (pinfunction "2_2") (pintype "passive"))
      (node (ref "C25") (pin "1") (pinfunction "1_1") (pintype "passive"))
      (node (ref "C26") (pin "1") (pinfunction "1_1") (pintype "passive"))
      (node (ref "C27") (pin "2") (pinfunction "2_2") (pintype "passive"))
      (node (ref "C3") (pin "1") (pinfunction "1_1") (pintype "passive"))
      (node (ref "C4") (pin "1") (pinfunction "1_1") (pintype "passive"))
      (node (ref "C6") (pin "1") (pinfunction "1_1") (pintype "passive"))
      (node (ref "C7") (pin "1") (pinfunction "1_1") (pintype "passive"))
      (node (ref "C8") (pin "1") (pinfunction "1_1") (pintype "passive"))
      (node (ref "C9") (pin "1") (pinfunction "1_1") (pintype "passive"))
      (node (ref "D3") (pin "2") (pinfunction "GND_2") (pintype "passive"))
      (node (ref "D4") (pin "1") (pinfunction "IO_1") (pintype "passive"))
      (node (ref "D5") (pin "1") (pinfunction "IO_1") (pintype "passive"))
      (node (ref "Down") (pin "2") (pintype "passive"))
      (node (ref "EN") (pin "1") (pinfunction "1_1") (pintype "passive"))
      (node (ref "J3") (pin "11") (pintype "passive"))
      (node (ref "J3") (pin "12") (pintype "passive"))
      (node (ref "J3") (pin "18") (pintype "passive"))
      (node (ref "Left") (pin "2") (pintype "passive"))
      (node (ref "Q3") (pin "2") (pinfunction "source_2") (pintype "passive"))
      (node (ref "R10") (pin "1") (pinfunction "1_1") (pintype "passive"))
      (node (ref "R11") (pin "2") (pinfunction "2_2") (pintype "passive"))
      (node (ref "R12") (pin "2") (pinfunction "2_2") (pintype "passive"))
      (node (ref "R14") (pin "2") (pinfunction "2_2") (pintype "passive"))
      (node (ref "R15") (pin "2") (pinfunction "2_2") (pintype "passive"))
      (node (ref "R17") (pin "1") (pinfunction "1_1") (pintype "passive"))
      (node (ref "R2") (pin "2") (pinfunction "2_2") (pintype "passive"))
      (node (ref "R22") (pin "1") (pinfunction "1_1") (pintype "passive"))
      (node (ref "R23") (pin "1") (pinfunction "1_1") (pintype "passive"))
      (node (ref "R26") (pin "1") (pinfunction "1_1") (pintype "passive"))
      (node (ref "R26") (pin "2") (pinfunction "2_2") (pintype "passive"))
      (node (ref "R6") (pin "1") (pinfunction "1_1") (pintype "passive"))
      (node (ref "R8") (pin "1") (pinfunction "1_1") (pintype "passive"))
      (node (ref "R9") (pin "1") (pinfunction "1_1") (pintype "passive"))
      (node (ref "Right") (pin "2") (pintype "passive"))
      (node (ref "Select") (pin "2") (pintype "passive"))
      (node (ref "Start") (pin "2") (pintype "passive"))
      (node (ref "TF1") (pin "10") (pinfunction "GND_10") (pintype "power_in"))
      (node (ref "TF1") (pin "11") (pinfunction "GND_11") (pintype "power_in"))
      (node (ref "TF1") (pin "12") (pinfunction "GND_12") (pintype "power_in"))
      (node (ref "TF1") (pin "13") (pinfunction "GND_13") (pintype "power_in"))
      (node (ref "TF1") (pin "2") (pinfunction "CD/DAT3_2") (pintype "input"))
      (node (ref "TF1") (pin "6") (pinfunction "VSS_6") (pintype "power_in"))
      (node (ref "U1") (pin "1") (pinfunction "GND_1") (pintype "power_in"))
      (node (ref "U1") (pin "15") (pinfunction "GND_15") (pintype "power_in"))
      (node (ref "U1") (pin "38") (pinfunction "GND_38") (pintype "power_in"))
      (node (ref "U2") (pin "17") (pinfunction "Thermal_Pad_17") (pintype "power_in"))
      (node (ref "U2") (pin "8") (pinfunction "VSS_8") (pintype "power_in"))
      (node (ref "U3") (pin "5") (pinfunction "GND_5") (pintype "power_in"))
      (node (ref "U4") (pin "1") (pinfunction "GND_1") (pintype "power_in"))
      (node (ref "U5") (pin "11") (pinfunction "GND_11") (pintype "power_in"))
      (node (ref "U5") (pin "15") (pinfunction "PGND_15") (pintype "power_in"))
      (node (ref "U5") (pin "2") (pinfunction "PGND_2") (pintype "power_in"))
      (node (ref "U6") (pin "4") (pinfunction "CS_4") (pintype "input"))
      (node (ref "U6") (pin "5") (pinfunction "CTR_5") (pintype "input"))
      (node (ref "U7") (pin "5") (pinfunction "GND_5") (pintype "power_in"))
      (node (ref "U7") (pin "6") (pinfunction "CG_6") (pintype "passive"))
      (node (ref "U7") (pin "7") (pinfunction "RSTIO_7") (pintype "bidirectional"))
      (node (ref "USB1") (pin "1") (pinfunction "EP_1") (pintype "passive"))
      (node (ref "USB1") (pin "2") (pinfunction "EP_2") (pintype "passive"))
      (node (ref "USB1") (pin "3") (pinfunction "EP_3") (pintype "passive"))
      (node (ref "USB1") (pin "4") (pinfunction "EP_4") (pintype "passive"))
      (node (ref "USB1") (pin "A1-B12") (pinfunction "GND_A1-B12") (pintype "power_in"))
      (node (ref "USB1") (pin "A12-B1") (pinfunction "GND_A12-B1") (pintype "power_in"))
      (node (ref "Up") (pin "2") (pintype "passive"))
    )
    (net (code "39") (name "Net-(C17-Pad1)") (class "Default")
      (node (ref "C17") (pin "1") (pinfunction "1_1") (pintype "passive"))
      (node (ref "R21") (pin "1") (pinfunction "1_1") (pintype "passive"))
    )
    (net (code "40") (name "Net-(D1-A)") (class "Default")
      (node (ref "D1") (pin "2") (pinfunction "A_2") (pintype "passive"))
      (node (ref "R3") (pin "1") (pinfunction "1_1") (pintype "passive"))
    )
    (net (code "41") (name "Net-(D1-C)") (class "Default")
      (node (ref "D1") (pin "1") (pinfunction "C_1") (pintype "passive"))
      (node (ref "U2") (pin "9") (pinfunction "~{CHG}_9") (pintype "tri_state"))
    )
    (net (code "42") (name "Net-(D2-A)") (class "Default")
      (node (ref "D2") (pin "2") (pinfunction "A_2") (pintype "passive"))
      (node (ref "R7") (pin "1") (pinfunction "1_1") (pintype "passive"))
    )
    (net (code "43") (name "Net-(D2-C)") (class "Default")
      (node (ref "D2") (pin "1") (pinfunction "C_1") (pintype "passive"))
      (node (ref "U2") (pin "7") (pinfunction "~{PGOOD}_7") (pintype "tri_state"))
    )
    (net (code "44") (name "Net-(F1-Pad1)") (class "Default")
      (node (ref "F1") (pin "1") (pinfunction "1_1") (pintype "passive"))
      (node (ref "J1") (pin "2") (pinfunction "2_2") (pintype "passive"))
    )
    (net (code "45") (name "Net-(F2-Pad1)") (class "Default")
      (node (ref "F2") (pin "1") (pinfunction "1_1") (pintype "passive"))
      (node (ref "USB1") (pin "A4-B9") (pinfunction "VBUS_A4-B9") (pintype "power_in"))
      (node (ref "USB1") (pin "A9-B4") (pinfunction "VBUS_A9-B4") (pintype "power_in"))
    )
    (net (code "46") (name "Net-(J3-Pad5)") (class "Default")
      (node (ref "J3") (pin "5") (pintype "passive"))
      (node (ref "J3") (pin "6") (pintype "passive"))
      (node (ref "J3") (pin "7") (pintype "passive"))
      (node (ref "J3") (pin "8") (pintype "passive"))
      (node (ref "R13") (pin "1") (pinfunction "1_1") (pintype "passive"))
    )
    (net (code "47") (name "Net-(Q3-drain)") (class "Default")
      (node (ref "Q3") (pin "3") (pinfunction "drain_3") (pintype "passive"))
      (node (ref "R13") (pin "2") (pinfunction "2_2") (pintype "passive"))
    )
    (net (code "48") (name "Net-(Q4-drain)") (class "Default")
      (node (ref "Q4") (pin "3") (pinfunction "drain_3") (pintype "passive"))
      (node (ref "Q5") (pin "2") (pinfunction "source_2") (pintype "passive"))
    )
    (net (code "49") (name "Net-(Q4-gate)") (class "Default")
      (node (ref "Q4") (pin "1") (pinfunction "gate_1") (pintype "passive"))
      (node (ref "U6") (pin "8") (pinfunction "CHG_8") (pintype "output"))
    )
    (net (code "50") (name "Net-(Q4-source)") (class "Default")
      (node (ref "F1") (pin "2") (pinfunction "2_2") (pintype "passive"))
      (node (ref "Q4") (pin "2") (pinfunction "source_2") (pintype "passive"))
      (node (ref "R1") (pin "2") (pinfunction "2_2") (pintype "passive"))
      (node (ref "R4") (pin "2") (pinfunction "2_2") (pintype "passive"))
    )
    (net (code "51") (name "Net-(Q5-gate)") (class "Default")
      (node (ref "Q5") (pin "1") (pinfunction "gate_1") (pintype "passive"))
      (node (ref "U6") (pin "7") (pinfunction "DSG_7") (pintype "output"))
    )
    (net (code "52") (name "Net-(R33-Pad2)") (class "Default")
      (node (ref "R33") (pin "2") (pinfunction "2_2") (pintype "passive"))
      (node (ref "R34") (pin "1") (pinfunction "1_1") (pintype "passive"))
    )
    (net (code "53") (name "Net-(T1-B)") (class "Default")
      (node (ref "R27") (pin "2") (pinfunction "2_2") (pintype "passive"))
      (node (ref "T1") (pin "1") (pinfunction "B_1") (pintype "passive"))
    )
    (net (code "54") (name "Net-(T2-B)") (class "Default")
      (node (ref "R31") (pin "2") (pinfunction "2_2") (pintype "passive"))
      (node (ref "T2") (pin "1") (pinfunction "B_1") (pintype "passive"))
    )
    (net (code "55") (name "Net-(U2-ILIM)") (class "Default")
      (node (ref "R2") (pin "1") (pinfunction "1_1") (pintype "passive"))
      (node (ref "U2") (pin "12") (pinfunction "ILIM_12") (pintype "input"))
    )
    (net (code "56") (name "Net-(U2-ISET)") (class "Default")
      (node (ref "R8") (pin "2") (pinfunction "2_2") (pintype "passive"))
      (node (ref "U2") (pin "16") (pinfunction "ISET_16") (pintype "input"))
    )
    (net (code "57") (name "Net-(U2-ITERM)") (class "Default")
      (node (ref "R6") (pin "2") (pinfunction "2_2") (pintype "passive"))
      (node (ref "U2") (pin "15") (pinfunction "ITERM_15") (pintype "input"))
    )
    (net (code "58") (name "Net-(U2-TS)") (class "Default")
      (node (ref "R11") (pin "1") (pinfunction "1_1") (pintype "passive"))
      (node (ref "U2") (pin "1") (pinfunction "TS_1") (pintype "input"))
    )
    (net (code "59") (name "Net-(U2-~{CE})") (class "Default")
      (node (ref "R12") (pin "1") (pinfunction "1_1") (pintype "passive"))
      (node (ref "U2") (pin "4") (pinfunction "~{CE}_4") (pintype "input"))
    )
    (net (code "60") (name "Net-(U3-EN)") (class "Default")
      (node (ref "C16") (pin "2") (pinfunction "2_2") (pintype "passive"))
      (node (ref "C21") (pin "1") (pinfunction "1_1") (pintype "passive"))
      (node (ref "PWR") (pin "1") (pinfunction "1_1") (pintype "passive"))
      (node (ref "U3") (pin "1") (pinfunction "EN_1") (pintype "input"))
      (node (ref "U3") (pin "7") (pinfunction "VIN_7") (pintype "power_in"))
    )
    (net (code "61") (name "Net-(U3-SW)") (class "Default")
      (node (ref "L1") (pin "1") (pinfunction "1_1") (pintype "passive"))
      (node (ref "U3") (pin "6") (pinfunction "SW_6") (pintype "output"))
    )
    (net (code "62") (name "Net-(U4-V3)") (class "Default")
      (node (ref "C27") (pin "1") (pinfunction "1_1") (pintype "passive"))
      (node (ref "U4") (pin "4") (pinfunction "V3_4") (pintype "input"))
    )
    (net (code "63") (name "Net-(U5-+OUT_L)") (class "Default")
      (node (ref "FB2") (pin "1") (pinfunction "1_1") (pintype "passive"))
      (node (ref "U5") (pin "1") (pinfunction "+OUT_L_1") (pintype "output"))
    )
    (net (code "64") (name "Net-(U5--OUT_L)") (class "Default")
      (node (ref "FB1") (pin "1") (pinfunction "1_1") (pintype "passive"))
      (node (ref "U5") (pin "3") (pinfunction "-OUT_L_3") (pintype "output"))
    )
    (net (code "65") (name "Net-(U5-INL)") (class "Default")
      (node (ref "R21") (pin "2") (pinfunction "2_2") (pintype "passive"))
      (node (ref "U5") (pin "7") (pinfunction "INL_7") (pintype "input"))
    )
    (net (code "66") (name "Net-(U5-INR)") (class "Default")
      (node (ref "R22") (pin "2") (pinfunction "2_2") (pintype "passive"))
      (node (ref "U5") (pin "10") (pinfunction "INR_10") (pintype "input"))
    )
    (net (code "67") (name "Net-(U5-VREF)") (class "Default")
      (node (ref "C18") (pin "2") (pinfunction "2_2") (pintype "passive"))
      (node (ref "U5") (pin "8") (pinfunction "VREF_8") (pintype "input"))
    )
    (net (code "68") (name "Net-(U6-BAT)") (class "Default")
      (node (ref "R4") (pin "1") (pinfunction "1_1") (pintype "passive"))
      (node (ref "U6") (pin "1") (pinfunction "BAT_1") (pintype "input"))
    )
    (net (code "69") (name "Net-(U6-PACK)") (class "Default")
      (node (ref "R5") (pin "1") (pinfunction "1_1") (pintype "passive"))
      (node (ref "U6") (pin "6") (pinfunction "PACK_6") (pintype "input"))
    )
    (net (code "70") (name "Net-(U6-VDD)") (class "Default")
      (node (ref "C5") (pin "2") (pinfunction "2_2") (pintype "passive"))
      (node (ref "R1") (pin "1") (pinfunction "1_1") (pintype "passive"))
      (node (ref "U6") (pin "2") (pinfunction "VDD_2") (pintype "power_in"))
    )
    (net (code "71") (name "Net-(U7-BATD{slash}CD)") (class "Default")
      (node (ref "R23") (pin "2") (pinfunction "2_2") (pintype "passive"))
      (node (ref "U7") (pin "8") (pinfunction "BATD/CD_8") (pintype "passive"))
    )
    (net (code "72") (name "Net-(U7-VIN)") (class "Default")
      (node (ref "C19") (pin "2") (pinfunction "2_2") (pintype "passive"))
      (node (ref "C20") (pin "2") (pinfunction "2_2") (pintype "passive"))
      (node (ref "R20") (pin "1") (pinfunction "1_1") (pintype "passive"))
      (node (ref "U7") (pin "10") (pinfunction "VIN_10") (pintype "passive"))
    )
    (net (code "73") (name "Net-(USB1-CC1)") (class "Default")
      (node (ref "R9") (pin "2") (pinfunction "2_2") (pintype "passive"))
      (node (ref "USB1") (pin "A5") (pinfunction "CC1_A5") (pintype "bidirectional"))
    )
    (net (code "74") (name "Net-(USB1-CC2)") (class "Default")
      (node (ref "R10") (pin "2") (pinfunction "2_2") (pintype "passive"))
      (node (ref "USB1") (pin "B5") (pinfunction "CC2_B5") (pintype "bidirectional"))
    )
    (net (code "75") (name "VBUS") (class "Default")
      (node (ref "C1") (pin "2") (pinfunction "2_2") (pintype "passive"))
      (node (ref "C2") (pin "1") (pinfunction "1_1") (pintype "passive"))
      (node (ref "D3") (pin "1") (pinfunction "IO_1") (pintype "passive"))
      (node (ref "F2") (pin "2") (pinfunction "2_2") (pintype "passive"))
      (node (ref "U2") (pin "13") (pinfunction "IN_13") (pintype "power_in"))
    )
    (net (code "76") (name "VSYS") (class "Default")
      (node (ref "C15") (pin "2") (pinfunction "2_2") (pintype "passive"))
      (node (ref "C3") (pin "2") (pinfunction "2_2") (pintype "passive"))
      (node (ref "PWR") (pin "2") (pinfunction "2_2") (pintype "passive"))
      (node (ref "R16") (pin "2") (pinfunction "2_2") (pintype "passive"))
      (node (ref "R3") (pin "2") (pinfunction "2_2") (pintype "passive"))
      (node (ref "R7") (pin "2") (pinfunction "2_2") (pintype "passive"))
      (node (ref "U2") (pin "10") (pinfunction "OUT_10") (pintype "power_in"))
      (node (ref "U2") (pin "11") (pinfunction "OUT_11") (pintype "power_in"))
    )
    (net (code "77") (name "unconnected-(J3-MP-Pad19)") (class "Default")
      (node (ref "J3") (pin "19") (pinfunction "MP_19") (pintype "passive+no_connect"))
    )
    (net (code "78") (name "unconnected-(J3-MP-Pad20)") (class "Default")
      (node (ref "J3") (pin "20") (pinfunction "MP_20") (pintype "passive+no_connect"))
    )
    (net (code "79") (name "unconnected-(J3-Pad1)") (class "Default")
      (node (ref "J3") (pin "1") (pintype "passive+no_connect"))
    )
    (net (code "80") (name "unconnected-(J3-Pad2)") (class "Default")
      (node (ref "J3") (pin "2") (pintype "passive+no_connect"))
    )
    (net (code "81") (name "unconnected-(J3-Pad3)") (class "Default")
      (node (ref "J3") (pin "3") (pintype "passive+no_connect"))
    )
    (net (code "82") (name "unconnected-(J3-Pad4)") (class "Default")
      (node (ref "J3") (pin "4") (pintype "passive+no_connect"))
    )
    (net (code "83") (name "unconnected-(PWR-MNT_1-Pad4)") (class "Default")
      (node (ref "PWR") (pin "4") (pinfunction "MNT_1_4") (pintype "passive+no_connect"))
    )
    (net (code "84") (name "unconnected-(PWR-MNT_2-Pad5)") (class "Default")
      (node (ref "PWR") (pin "5") (pinfunction "MNT_2_5") (pintype "passive+no_connect"))
    )
    (net (code "85") (name "unconnected-(PWR-MNT_3-Pad6)") (class "Default")
      (node (ref "PWR") (pin "6") (pinfunction "MNT_3_6") (pintype "passive+no_connect"))
    )
    (net (code "86") (name "unconnected-(PWR-MNT_4-Pad7)") (class "Default")
      (node (ref "PWR") (pin "7") (pinfunction "MNT_4_7") (pintype "passive+no_connect"))
    )
    (net (code "87") (name "unconnected-(PWR-Pad3)") (class "Default")
      (node (ref "PWR") (pin "3") (pinfunction "3_3") (pintype "passive+no_connect"))
    )
    (net (code "88") (name "unconnected-(TF1-CD-Pad9)") (class "Default")
      (node (ref "TF1") (pin "9") (pinfunction "CD_9") (pintype "input+no_connect"))
    )
    (net (code "89") (name "unconnected-(TF1-DAT1-Pad8)") (class "Default")
      (node (ref "TF1") (pin "8") (pinfunction "DAT1_8") (pintype "input+no_connect"))
    )
    (net (code "90") (name "unconnected-(TF1-DAT2-Pad1)") (class "Default")
      (node (ref "TF1") (pin "1") (pinfunction "DAT2_1") (pintype "input+no_connect"))
    )
    (net (code "91") (name "unconnected-(U1-IO34-Pad6)") (class "Default")
      (node (ref "U1") (pin "6") (pinfunction "IO34_6") (pintype "input+no_connect"))
    )
    (net (code "92") (name "unconnected-(U1-IO35-Pad7)") (class "Default")
      (node (ref "U1") (pin "7") (pinfunction "IO35_7") (pintype "input+no_connect"))
    )
    (net (code "93") (name "unconnected-(U1-NC-Pad17)") (class "Default")
      (node (ref "U1") (pin "17") (pinfunction "NC_17") (pintype "passive+no_connect"))
    )
    (net (code "94") (name "unconnected-(U1-NC-Pad18)") (class "Default")
      (node (ref "U1") (pin "18") (pinfunction "NC_18") (pintype "passive+no_connect"))
    )
    (net (code "95") (name "unconnected-(U1-NC-Pad19)") (class "Default")
      (node (ref "U1") (pin "19") (pinfunction "NC_19") (pintype "passive+no_connect"))
    )
    (net (code "96") (name "unconnected-(U1-NC-Pad20)") (class "Default")
      (node (ref "U1") (pin "20") (pinfunction "NC_20") (pintype "passive+no_connect"))
    )
    (net (code "97") (name "unconnected-(U1-NC-Pad21)") (class "Default")
      (node (ref "U1") (pin "21") (pinfunction "NC_21") (pintype "passive+no_connect"))
    )
    (net (code "98") (name "unconnected-(U1-NC-Pad22)") (class "Default")
      (node (ref "U1") (pin "22") (pinfunction "NC_22") (pintype "passive+no_connect"))
    )
    (net (code "99") (name "unconnected-(U1-NC-Pad32)") (class "Default")
      (node (ref "U1") (pin "32") (pinfunction "NC_32") (pintype "passive+no_connect"))
    )
    (net (code "100") (name "unconnected-(U1-SENSOR_VN-Pad5)") (class "Default")
      (node (ref "U1") (pin "5") (pinfunction "SENSOR_VN_5") (pintype "input+no_connect"))
    )
    (net (code "101") (name "unconnected-(U1-SENSOR_VP-Pad4)") (class "Default")
      (node (ref "U1") (pin "4") (pinfunction "SENSOR_VP_4") (pintype "input+no_connect"))
    )
    (net (code "102") (name "unconnected-(U2-TMR-Pad14)") (class "Default")
      (node (ref "U2") (pin "14") (pinfunction "TMR_14") (pintype "input+no_connect"))
    )
    (net (code "103") (name "unconnected-(U3-PG-Pad2)") (class "Default")
      (node (ref "U3") (pin "2") (pinfunction "PG_2") (pintype "output+no_connect"))
    )
    (net (code "104") (name "unconnected-(U4-CTS#-Pad9)") (class "Default")
      (node (ref "U4") (pin "9") (pinfunction "CTS#_9") (pintype "input+no_connect"))
    )
    (net (code "105") (name "unconnected-(U4-DCD#-Pad12)") (class "Default")
      (node (ref "U4") (pin "12") (pinfunction "DCD#_12") (pintype "input+no_connect"))
    )
    (net (code "106") (name "unconnected-(U4-DSR#-Pad10)") (class "Default")
      (node (ref "U4") (pin "10") (pinfunction "DSR#_10") (pintype "input+no_connect"))
    )
    (net (code "107") (name "unconnected-(U4-NC-Pad7)") (class "Default")
      (node (ref "U4") (pin "7") (pinfunction "NC_7") (pintype "input+no_connect"))
    )
    (net (code "108") (name "unconnected-(U4-OUT#-Pad8)") (class "Default")
      (node (ref "U4") (pin "8") (pinfunction "OUT#_8") (pintype "input+no_connect"))
    )
    (net (code "109") (name "unconnected-(U4-R232-Pad15)") (class "Default")
      (node (ref "U4") (pin "15") (pinfunction "R232_15") (pintype "input+no_connect"))
    )
    (net (code "110") (name "unconnected-(U4-RI#-Pad11)") (class "Default")
      (node (ref "U4") (pin "11") (pinfunction "RI#_11") (pintype "input+no_connect"))
    )
    (net (code "111") (name "unconnected-(U5-+OUT_R-Pad16)") (class "Default")
      (node (ref "U5") (pin "16") (pinfunction "+OUT_R_16") (pintype "output+no_connect"))
    )
    (net (code "112") (name "unconnected-(U5--OUT_R-Pad14)") (class "Default")
      (node (ref "U5") (pin "14") (pinfunction "-OUT_R_14") (pintype "output+no_connect"))
    )
    (net (code "113") (name "unconnected-(U5-MUTE-Pad5)") (class "Default")
      (node (ref "U5") (pin "5") (pinfunction "MUTE_5") (pintype "input+no_connect"))
    )
    (net (code "114") (name "unconnected-(U5-SHND-Pad12)") (class "Default")
      (node (ref "U5") (pin "12") (pinfunction "SHND_12") (pintype "input+no_connect"))
    )
    (net (code "115") (name "unconnected-(U7-ALM-Pad1)") (class "Default")
      (node (ref "U7") (pin "1") (pinfunction "ALM_1") (pintype "open_collector+no_connect"))
    )
    (net (code "116") (name "unconnected-(U7-NC-Pad4)") (class "Default")
      (node (ref "U7") (pin "4") (pinfunction "NC_4") (pintype "passive+no_connect"))
    )
    (net (code "117") (name "unconnected-(USB1-SBU1-PadA8)") (class "Default")
      (node (ref "USB1") (pin "A8") (pinfunction "SBU1_A8") (pintype "bidirectional+no_connect"))
    )
    (net (code "118") (name "unconnected-(USB1-SBU2-PadB8)") (class "Default")
      (node (ref "USB1") (pin "B8") (pinfunction "SBU2_B8") (pintype "bidirectional+no_connect"))
    )
  )
)
